# Proyecto_DE.net
KiCad netlist of a schematic drawn in EAGLE
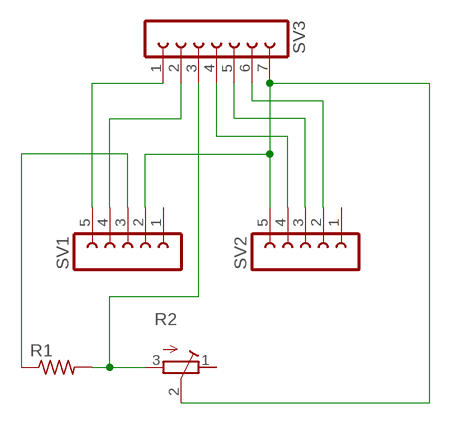
[diagram p0: schematic, sheet 1]

(export (version "E")
  (design (tool "Eeschema 10.0.6"))
  (components
    (comp (ref "R1")
      (value "R-US_0207/12")
      (footprint "eagle-import:0207_12")
      (libsource (lib "eagle-import") (part "R-US_0207/12"))
    )
    (comp (ref "R2")
      (value "R-TRIMMT93YA")
      (footprint "eagle-import:RTRIMT93YA")
      (libsource (lib "eagle-import") (part "R-TRIMMT93YA"))
    )
    (comp (ref "SV1")
      (value "FE05-1")
      (footprint "eagle-import:FE05-1")
      (libsource (lib "eagle-import") (part "FE05-1"))
    )
    (comp (ref "SV2")
      (value "FE05-1")
      (footprint "eagle-import:FE05-1")
      (libsource (lib "eagle-import") (part "FE05-1"))
    )
    (comp (ref "SV3")
      (value "FE07-1")
      (footprint "eagle-import:FE07")
      (libsource (lib "eagle-import") (part "FE07-1"))
    )
  )
  (nets
    (net (code "1") (name "Net-(R1-Pad1)") (class "Default")
      (node (ref "R1") (pin "1") (pinfunction "1_1") (pintype "passive"))
      (node (ref "SV1") (pin "3") (pinfunction "3_3") (pintype "passive"))
    )
    (net (code "2") (name "Net-(R2-A)") (class "Default")
      (node (ref "R1") (pin "2") (pinfunction "2_2") (pintype "passive"))
      (node (ref "R2") (pin "3") (pinfunction "A_3") (pintype "passive"))
      (node (ref "SV3") (pin "3") (pinfunction "3_3") (pintype "passive"))
    )
    (net (code "3") (name "Net-(R2-S)") (class "Default")
      (node (ref "R2") (pin "2") (pinfunction "S_2") (pintype "passive"))
      (node (ref "SV1") (pin "2") (pinfunction "2_2") (pintype "passive"))
      (node (ref "SV2") (pin "5") (pinfunction "5_5") (pintype "passive"))
      (node (ref "SV3") (pin "7") (pinfunction "7_7") (pintype "passive"))
    )
    (net (code "4") (name "Net-(SV1-Pad4)") (class "Default")
      (node (ref "SV1") (pin "4") (pinfunction "4_4") (pintype "passive"))
      (node (ref "SV3") (pin "2") (pinfunction "2_2") (pintype "passive"))
    )
    (net (code "5") (name "Net-(SV1-Pad5)") (class "Default")
      (node (ref "SV1") (pin "5") (pinfunction "5_5") (pintype "passive"))
      (node (ref "SV3") (pin "1") (pinfunction "1_1") (pintype "passive"))
    )
    (net (code "6") (name "Net-(SV2-Pad2)") (class "Default")
      (node (ref "SV2") (pin "2") (pinfunction "2_2") (pintype "passive"))
      (node (ref "SV3") (pin "6") (pinfunction "6_6") (pintype "passive"))
    )
    (net (code "7") (name "Net-(SV2-Pad3)") (class "Default")
      (node (ref "SV2") (pin "3") (pinfunction "3_3") (pintype "passive"))
      (node (ref "SV3") (pin "5") (pinfunction "5_5") (pintype "passive"))
    )
    (net (code "8") (name "Net-(SV2-Pad4)") (class "Default")
      (node (ref "SV2") (pin "4") (pinfunction "4_4") (pintype "passive"))
      (node (ref "SV3") (pin "4") (pinfunction "4_4") (pintype "passive"))
    )
    (net (code "9") (name "unconnected-(R2-E-Pad1)") (class "Default")
      (node (ref "R2") (pin "1") (pinfunction "E_1") (pintype "passive"))
    )
    (net (code "10") (name "unconnected-(SV1-Pad1)") (class "Default")
      (node (ref "SV1") (pin "1") (pinfunction "1_1") (pintype "passive"))
    )
    (net (code "11") (name "unconnected-(SV2-Pad1)") (class "Default")
      (node (ref "SV2") (pin "1") (pinfunction "1_1") (pintype "passive"))
    )
  )
)
